# Parallel_Drives.net
KiCad netlist of a schematic drawn in EAGLE
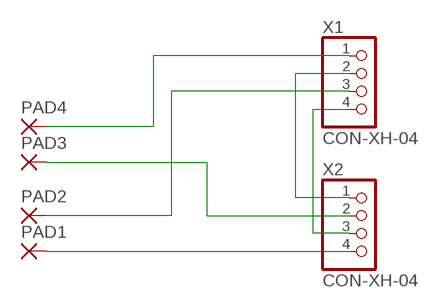
[diagram p0: schematic, sheet 1]

(export (version "E")
  (design (tool "Eeschema 10.0.6"))
  (components
    (comp (ref "PAD1")
      (value "SMD2")
      (footprint "eagle-import:SMD1,27-2,54")
      (libsource (lib "eagle-import") (part "SMD2"))
    )
    (comp (ref "PAD2")
      (value "SMD2")
      (footprint "eagle-import:SMD1,27-2,54")
      (libsource (lib "eagle-import") (part "SMD2"))
    )
    (comp (ref "PAD3")
      (value "SMD2")
      (footprint "eagle-import:SMD1,27-2,54")
      (libsource (lib "eagle-import") (part "SMD2"))
    )
    (comp (ref "PAD4")
      (value "SMD2")
      (footprint "eagle-import:SMD1,27-2,54")
      (libsource (lib "eagle-import") (part "SMD2"))
    )
    (comp (ref "X1")
      (value "CON-XH-04")
      (footprint "eagle-import:XH-04")
      (libsource (lib "eagle-import") (part "CON-XH-04"))
    )
    (comp (ref "X2")
      (value "CON-XH-04")
      (footprint "eagle-import:XH-04")
      (libsource (lib "eagle-import") (part "CON-XH-04"))
    )
  )
  (nets
    (net (code "1") (name "Net-(PAD1-P)") (class "Default")
      (node (ref "PAD1") (pin "1") (pinfunction "P_1") (pintype "passive"))
      (node (ref "X2") (pin "4") (pinfunction "4_4") (pintype "passive"))
    )
    (net (code "2") (name "Net-(PAD2-P)") (class "Default")
      (node (ref "PAD2") (pin "1") (pinfunction "P_1") (pintype "passive"))
      (node (ref "X1") (pin "3") (pinfunction "3_3") (pintype "passive"))
    )
    (net (code "3") (name "Net-(PAD3-P)") (class "Default")
      (node (ref "PAD3") (pin "1") (pinfunction "P_1") (pintype "passive"))
      (node (ref "X2") (pin "2") (pinfunction "2_2") (pintype "passive"))
    )
    (net (code "4") (name "Net-(PAD4-P)") (class "Default")
      (node (ref "PAD4") (pin "1") (pinfunction "P_1") (pintype "passive"))
      (node (ref "X1") (pin "1") (pinfunction "1_1") (pintype "passive"))
    )
    (net (code "5") (name "Net-(X1-Pad2)") (class "Default")
      (node (ref "X1") (pin "2") (pinfunction "2_2") (pintype "passive"))
      (node (ref "X2") (pin "1") (pinfunction "1_1") (pintype "passive"))
    )
    (net (code "6") (name "Net-(X1-Pad4)") (class "Default")
      (node (ref "X1") (pin "4") (pinfunction "4_4") (pintype "passive"))
      (node (ref "X2") (pin "3") (pinfunction "3_3") (pintype "passive"))
    )
  )
)
